# Bluetooth.net
KiCad netlist of a schematic drawn in Altium Designer
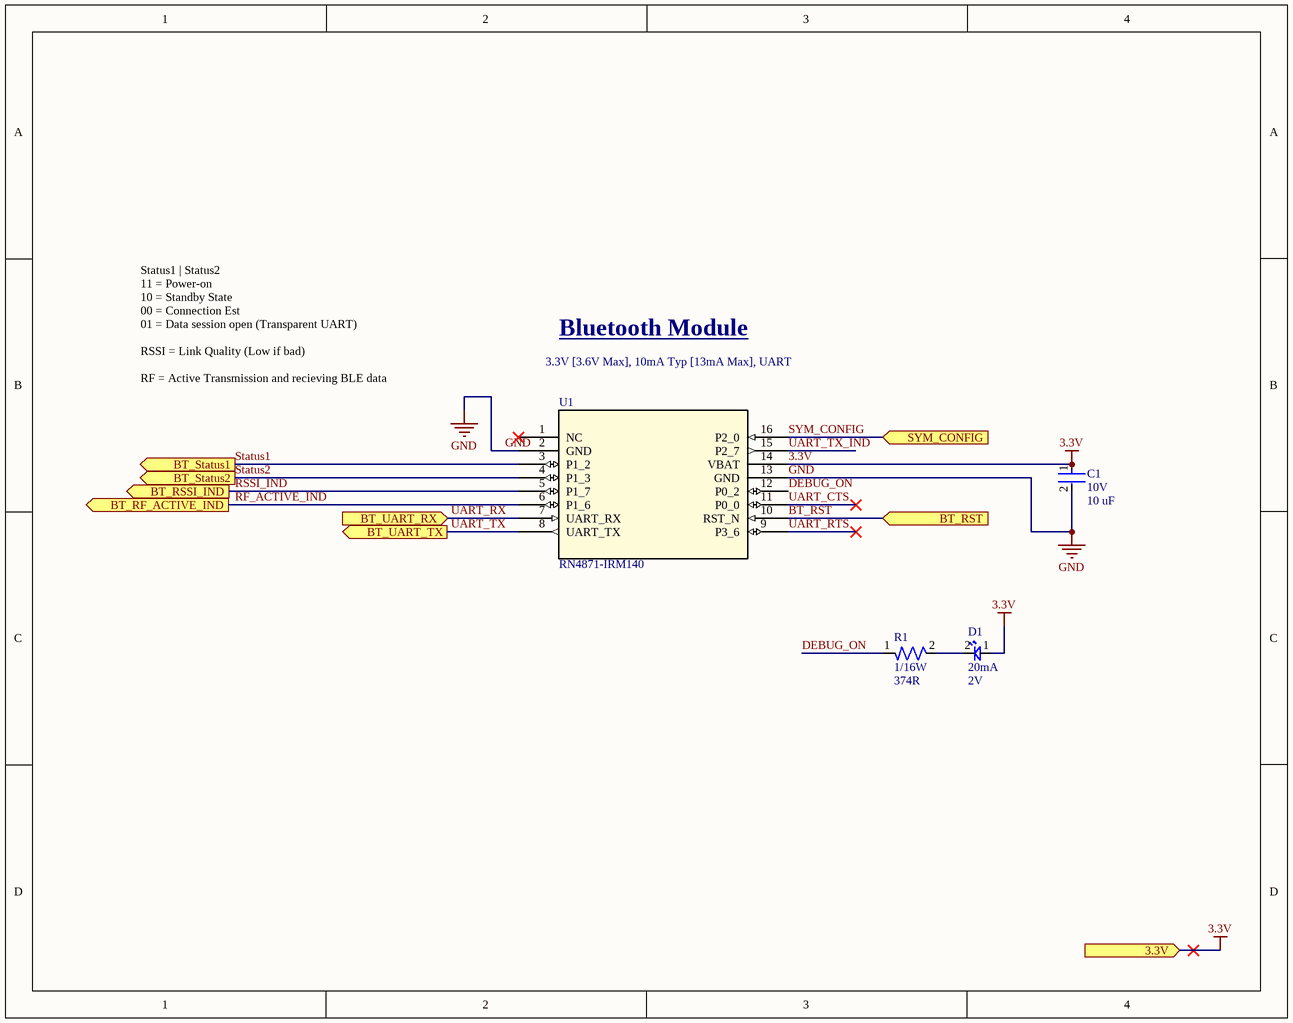
[diagram p0: Bluetooth.SchDoc]

(export (version "E")
  (design (tool "Eeschema 10.0.6"))
  (components
    (comp (ref "C1")
      (value "CC0603KRX5R6BB106")
      (footprint "CAP-0603")
      (description "CAP CER 10UF 10V X5R 0603")
      (fields (field (name "VOLTAGE") "10V") (field (name "CAPACITANCE") "10 uF"))
      (libsource (lib "JLC_25") (part "CAP-10U-0001"))
    )
    (comp (ref "D1")
      (value "150060AS75000")
      (footprint "LED-0603")
      (description "CAP CER 0.1UF 100V X7R 0603")
      (fields
        (field (name "MANUFACTURER") "Wurth Electronik")
        (field (name "CURRENT RATING") "20mA")
        (field (name "VF") "2V")
      )
      (libsource (lib "MasterLib") (part "LED_Amber_0001"))
    )
    (comp (ref "R1")
      (value "RC0402FR-07374RL")
      (footprint "RES-0402")
      (description "RES 374 OHM 1% 1/16W 0402")
      (fields
        (field (name "TOLERANCE") "1%")
        (field (name "POWER") "1/16W")
        (field (name "RESISTANCE") "374R")
      )
      (libsource (lib "JLC_25") (part "RES-374-0001"))
    )
    (comp (ref "U1")
      (value "RN4871-IRM140")
      (footprint "RN4871_MCH")
      (description "Bluetooth Bluetooth v5.0 Transceiver Module 2.402GHz ~ 2.48GHz Integrated, Chip Surface Mount")
      (libsource (lib "eecs373Lib") (part "IC-Bluetooth-2"))
    )
  )
  (nets
    (net (code "1") (name "/BT_RST") (class "Default")
      (node (ref "U1") (pin "10") (pinfunction "RST_N_10") (pintype "input"))
    )
    (net (code "2") (name "/DEBUG_ON") (class "Default")
      (node (ref "R1") (pin "1") (pinfunction "1_1") (pintype "passive"))
      (node (ref "U1") (pin "12") (pinfunction "P0_2_12") (pintype "bidirectional"))
    )
    (net (code "3") (name "/RF_ACTIVE_IND") (class "Default")
      (node (ref "U1") (pin "6") (pinfunction "P1_6_6") (pintype "bidirectional"))
    )
    (net (code "4") (name "/RSSI_IND") (class "Default")
      (node (ref "U1") (pin "5") (pinfunction "P1_7_5") (pintype "bidirectional"))
    )
    (net (code "5") (name "/SYM_CONFIG") (class "Default")
      (node (ref "U1") (pin "16") (pinfunction "P2_0_16") (pintype "input"))
    )
    (net (code "6") (name "/Status1") (class "Default")
      (node (ref "U1") (pin "3") (pinfunction "P1_2_3") (pintype "bidirectional"))
    )
    (net (code "7") (name "/Status2") (class "Default")
      (node (ref "U1") (pin "4") (pinfunction "P1_3_4") (pintype "bidirectional"))
    )
    (net (code "8") (name "/UART_CTS") (class "Default")
      (node (ref "U1") (pin "11") (pinfunction "P0_0_11") (pintype "bidirectional+no_connect"))
    )
    (net (code "9") (name "/UART_RTS") (class "Default")
      (node (ref "U1") (pin "9") (pinfunction "P3_6_9") (pintype "bidirectional+no_connect"))
    )
    (net (code "10") (name "/UART_RX") (class "Default")
      (node (ref "U1") (pin "7") (pinfunction "UART_RX_7") (pintype "input"))
    )
    (net (code "11") (name "/UART_TX") (class "Default")
      (node (ref "U1") (pin "8") (pinfunction "UART_TX_8") (pintype "output"))
    )
    (net (code "12") (name "/UART_TX_IND") (class "Default")
      (node (ref "U1") (pin "15") (pinfunction "P2_7_15") (pintype "output"))
    )
    (net (code "13") (name "3.3V") (class "Default")
      (node (ref "C1") (pin "1") (pinfunction "1_1") (pintype "passive"))
      (node (ref "D1") (pin "1") (pinfunction "1_1") (pintype "passive"))
      (node (ref "U1") (pin "14") (pinfunction "VBAT_14") (pintype "power_in"))
    )
    (net (code "14") (name "GND") (class "Default")
      (node (ref "C1") (pin "2") (pinfunction "2_2") (pintype "passive"))
      (node (ref "U1") (pin "13") (pinfunction "GND_13") (pintype "power_in"))
      (node (ref "U1") (pin "2") (pinfunction "GND_2") (pintype "power_in"))
    )
    (net (code "15") (name "Net-(D1-Pad2)") (class "Default")
      (node (ref "D1") (pin "2") (pinfunction "2_2") (pintype "passive"))
      (node (ref "R1") (pin "2") (pinfunction "2_2") (pintype "passive"))
    )
    (net (code "16") (name "unconnected-(U1-NC-Pad1)") (class "Default")
      (node (ref "U1") (pin "1") (pinfunction "NC_1") (pintype "passive+no_connect"))
    )
  )
)
